# butter.net
KiCad netlist of a schematic drawn in EAGLE
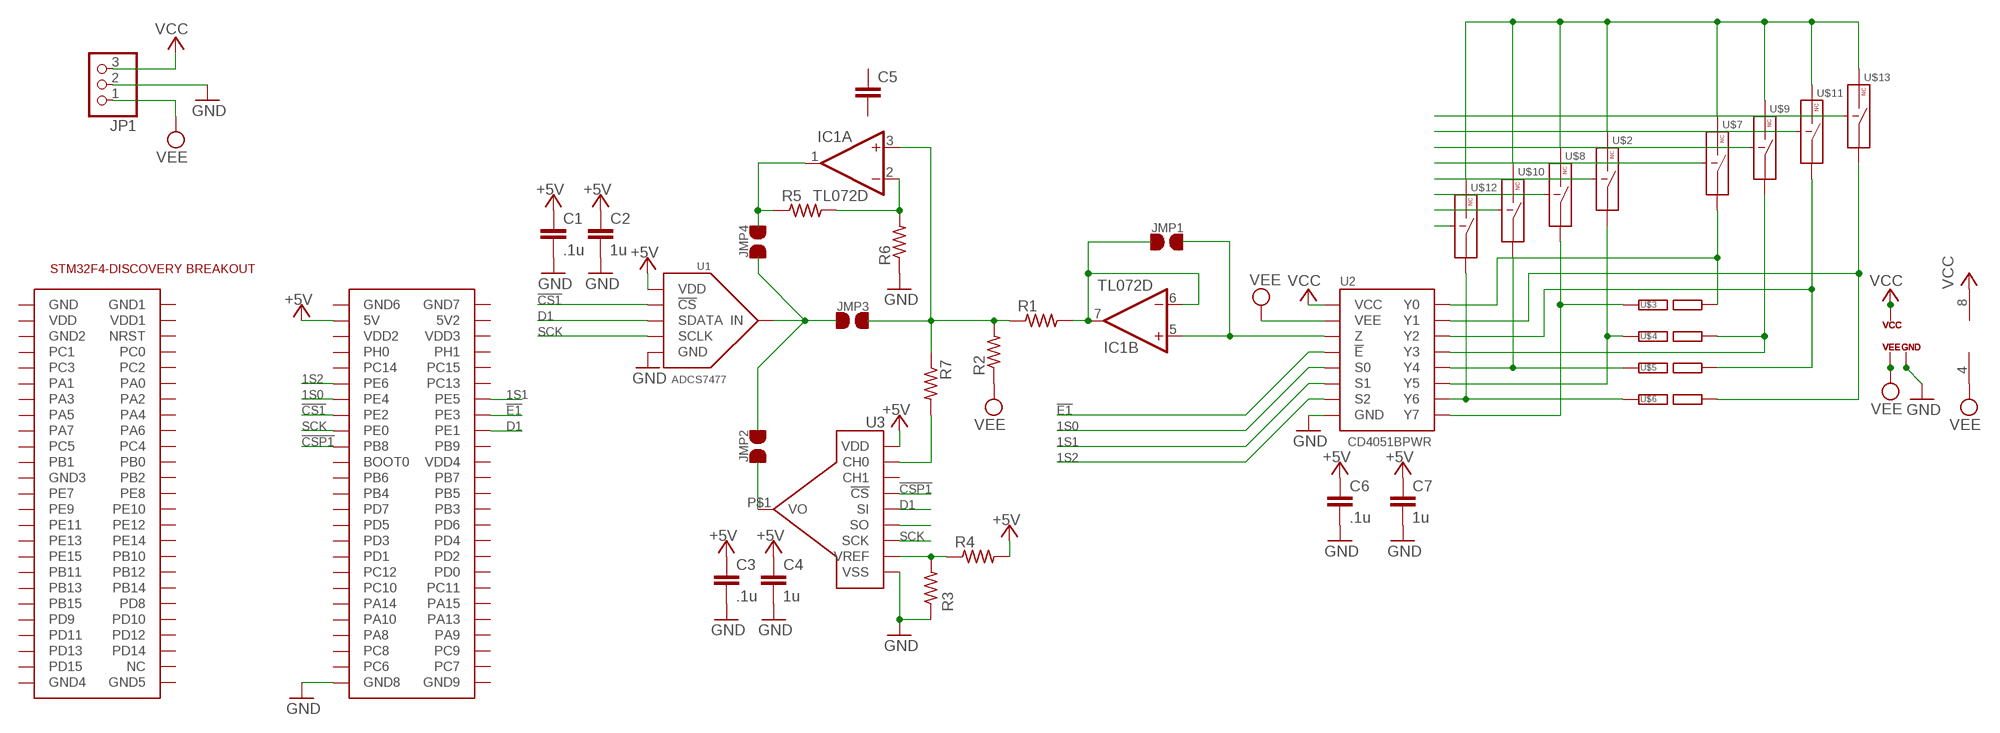
[diagram p0: schematic, sheet 1]

(export (version "E")
  (design (tool "Eeschema 10.0.6"))
  (components
    (comp (ref "C1")
      (value ".1u")
      (footprint "eagle-import:C0805")
      (libsource (lib "eagle-import") (part "C-EUC0805"))
    )
    (comp (ref "C2")
      (value "1u")
      (footprint "eagle-import:C0805")
      (libsource (lib "eagle-import") (part "C-EUC0805"))
    )
    (comp (ref "C3")
      (value ".1u")
      (footprint "eagle-import:C0805")
      (libsource (lib "eagle-import") (part "C-EUC0805"))
    )
    (comp (ref "C4")
      (value "1u")
      (footprint "eagle-import:C0805")
      (libsource (lib "eagle-import") (part "C-EUC0805"))
    )
    (comp (ref "C5")
      (value "C-EUC0805")
      (footprint "eagle-import:C0805")
      (libsource (lib "eagle-import") (part "C-EUC0805"))
    )
    (comp (ref "C6")
      (value ".1u")
      (footprint "eagle-import:C0805")
      (libsource (lib "eagle-import") (part "C-EUC0805"))
    )
    (comp (ref "C7")
      (value "1u")
      (footprint "eagle-import:C0805")
      (libsource (lib "eagle-import") (part "C-EUC0805"))
    )
    (comp (ref "IC1")
      (value "TL072D")
      (footprint "eagle-import:SO08")
      (libsource (lib "eagle-import") (part "TL072D"))
    )
    (comp (ref "JMP1")
      (value "JMP")
      (footprint "eagle-import:JMP")
      (libsource (lib "eagle-import") (part "JMP"))
    )
    (comp (ref "JMP2")
      (value "JMP")
      (footprint "eagle-import:JMP")
      (libsource (lib "eagle-import") (part "JMP"))
    )
    (comp (ref "JMP3")
      (value "JMP")
      (footprint "eagle-import:JMP")
      (libsource (lib "eagle-import") (part "JMP"))
    )
    (comp (ref "JMP4")
      (value "JMP")
      (footprint "eagle-import:JMP")
      (libsource (lib "eagle-import") (part "JMP"))
    )
    (comp (ref "JP1")
      (value "PINHD-1X3")
      (footprint "eagle-import:1X03")
      (libsource (lib "eagle-import") (part "PINHD-1X3"))
    )
    (comp (ref "R1")
      (value "R-US_R0603")
      (footprint "eagle-import:R0603")
      (libsource (lib "eagle-import") (part "R-US_R0603"))
    )
    (comp (ref "R2")
      (value "R-US_R0603")
      (footprint "eagle-import:R0603")
      (libsource (lib "eagle-import") (part "R-US_R0603"))
    )
    (comp (ref "R3")
      (value "R-US_R0603")
      (footprint "eagle-import:R0603")
      (libsource (lib "eagle-import") (part "R-US_R0603"))
    )
    (comp (ref "R4")
      (value "R-US_R0603")
      (footprint "eagle-import:R0603")
      (libsource (lib "eagle-import") (part "R-US_R0603"))
    )
    (comp (ref "R5")
      (value "R-US_R0603")
      (footprint "eagle-import:R0603")
      (libsource (lib "eagle-import") (part "R-US_R0603"))
    )
    (comp (ref "R6")
      (value "R-US_R0603")
      (footprint "eagle-import:R0603")
      (libsource (lib "eagle-import") (part "R-US_R0603"))
    )
    (comp (ref "R7")
      (value "R-US_R0603")
      (footprint "eagle-import:R0603")
      (libsource (lib "eagle-import") (part "R-US_R0603"))
    )
    (comp (ref "U$1")
      (value "STM32F4-DISCOVERY")
      (footprint "eagle-import:STM32F4-DISCOVERY")
      (libsource (lib "eagle-import") (part "STM32F4-DISCOVERY"))
    )
    (comp (ref "U$2")
      (value "DG467")
      (footprint "eagle-import:TSSOP-6")
      (libsource (lib "eagle-import") (part "DG467"))
    )
    (comp (ref "U$3")
      (value "RAILSEP")
      (footprint "eagle-import:RAIL")
      (libsource (lib "eagle-import") (part "RAILSEP"))
    )
    (comp (ref "U$4")
      (value "RAILSEP")
      (footprint "eagle-import:RAIL")
      (libsource (lib "eagle-import") (part "RAILSEP"))
    )
    (comp (ref "U$5")
      (value "RAILSEP")
      (footprint "eagle-import:RAIL")
      (libsource (lib "eagle-import") (part "RAILSEP"))
    )
    (comp (ref "U$6")
      (value "RAILSEP")
      (footprint "eagle-import:RAIL")
      (libsource (lib "eagle-import") (part "RAILSEP"))
    )
    (comp (ref "U$7")
      (value "DG467")
      (footprint "eagle-import:TSSOP-6")
      (libsource (lib "eagle-import") (part "DG467"))
    )
    (comp (ref "U$8")
      (value "DG467")
      (footprint "eagle-import:TSSOP-6")
      (libsource (lib "eagle-import") (part "DG467"))
    )
    (comp (ref "U$9")
      (value "DG467")
      (footprint "eagle-import:TSSOP-6")
      (libsource (lib "eagle-import") (part "DG467"))
    )
    (comp (ref "U$10")
      (value "DG467")
      (footprint "eagle-import:TSSOP-6")
      (libsource (lib "eagle-import") (part "DG467"))
    )
    (comp (ref "U$11")
      (value "DG467")
      (footprint "eagle-import:TSSOP-6")
      (libsource (lib "eagle-import") (part "DG467"))
    )
    (comp (ref "U$12")
      (value "DG467")
      (footprint "eagle-import:TSSOP-6")
      (libsource (lib "eagle-import") (part "DG467"))
    )
    (comp (ref "U$13")
      (value "DG467")
      (footprint "eagle-import:TSSOP-6")
      (libsource (lib "eagle-import") (part "DG467"))
    )
    (comp (ref "U1")
      (value "ADCS7477")
      (footprint "eagle-import:SOT-23-6")
      (libsource (lib "eagle-import") (part "ADCS7477"))
    )
    (comp (ref "U2")
      (value "CD4051BPWR")
      (footprint "eagle-import:TSSOP-16")
      (libsource (lib "eagle-import") (part "CD4051BPWR"))
    )
    (comp (ref "U3")
      (value "MCP6S93")
      (footprint "eagle-import:MSOP-10")
      (libsource (lib "eagle-import") (part "MCP6S93"))
    )
  )
  (nets
    (net (code "1") (name "+5V") (class "Default")
      (node (ref "C1") (pin "1") (pinfunction "1_1") (pintype "passive"))
      (node (ref "C2") (pin "1") (pinfunction "1_1") (pintype "passive"))
      (node (ref "C3") (pin "1") (pinfunction "1_1") (pintype "passive"))
      (node (ref "C4") (pin "1") (pinfunction "1_1") (pintype "passive"))
      (node (ref "C6") (pin "1") (pinfunction "1_1") (pintype "passive"))
      (node (ref "C7") (pin "1") (pinfunction "1_1") (pintype "passive"))
      (node (ref "R4") (pin "2") (pinfunction "2_2") (pintype "passive"))
      (node (ref "U$1") (pin "P$53") (pinfunction "5V_P$53") (pintype "bidirectional"))
      (node (ref "U1") (pin "P$1") (pinfunction "VDD_P$1") (pintype "bidirectional"))
      (node (ref "U3") (pin "P$10") (pinfunction "VDD_P$10") (pintype "bidirectional"))
    )
    (net (code "2") (name "/1S0") (class "Default")
      (node (ref "U$1") (pin "P$63") (pinfunction "PE4_P$63") (pintype "bidirectional"))
      (node (ref "U2") (pin "P$11") (pinfunction "S0_P$11") (pintype "bidirectional"))
    )
    (net (code "3") (name "/1S1") (class "Default")
      (node (ref "U$1") (pin "P$64") (pinfunction "PE5_P$64") (pintype "bidirectional"))
      (node (ref "U2") (pin "P$10") (pinfunction "S1_P$10") (pintype "bidirectional"))
    )
    (net (code "4") (name "/1S2") (class "Default")
      (node (ref "U$1") (pin "P$61") (pinfunction "PE6_P$61") (pintype "bidirectional"))
      (node (ref "U2") (pin "P$9") (pinfunction "S2_P$9") (pintype "bidirectional"))
    )
    (net (code "5") (name "/D1") (class "Default")
      (node (ref "U$1") (pin "P$68") (pinfunction "PE1_P$68") (pintype "bidirectional"))
      (node (ref "U1") (pin "P$5") (pinfunction "SDATA_P$5") (pintype "bidirectional"))
      (node (ref "U3") (pin "P$7") (pinfunction "SI_P$7") (pintype "bidirectional"))
    )
    (net (code "6") (name "/SCK") (class "Default")
      (node (ref "U$1") (pin "P$67") (pinfunction "PE0_P$67") (pintype "bidirectional"))
      (node (ref "U1") (pin "P$4") (pinfunction "SCLK_P$4") (pintype "bidirectional"))
      (node (ref "U3") (pin "P$9") (pinfunction "SCK_P$9") (pintype "bidirectional"))
    )
    (net (code "7") (name "/~{CS1}") (class "Default")
      (node (ref "U$1") (pin "P$65") (pinfunction "PE2_P$65") (pintype "bidirectional"))
      (node (ref "U1") (pin "P$6") (pinfunction "~{CS}_P$6") (pintype "bidirectional"))
    )
    (net (code "8") (name "/~{CSP1}") (class "Default")
      (node (ref "U$1") (pin "P$69") (pinfunction "PB8_P$69") (pintype "bidirectional"))
      (node (ref "U3") (pin "P$6") (pinfunction "~{CS}_P$6") (pintype "bidirectional"))
    )
    (net (code "9") (name "/~{E1}") (class "Default")
      (node (ref "U$1") (pin "P$66") (pinfunction "PE3_P$66") (pintype "bidirectional"))
      (node (ref "U2") (pin "P$6") (pinfunction "~{E}_P$6") (pintype "bidirectional"))
    )
    (net (code "10") (name "GND") (class "Default")
      (node (ref "C1") (pin "2") (pinfunction "2_2") (pintype "passive"))
      (node (ref "C2") (pin "2") (pinfunction "2_2") (pintype "passive"))
      (node (ref "C3") (pin "2") (pinfunction "2_2") (pintype "passive"))
      (node (ref "C4") (pin "2") (pinfunction "2_2") (pintype "passive"))
      (node (ref "C6") (pin "2") (pinfunction "2_2") (pintype "passive"))
      (node (ref "C7") (pin "2") (pinfunction "2_2") (pintype "passive"))
      (node (ref "JP1") (pin "2") (pinfunction "2_2") (pintype "passive"))
      (node (ref "R3") (pin "1") (pinfunction "1_1") (pintype "passive"))
      (node (ref "R6") (pin "1") (pinfunction "1_1") (pintype "passive"))
      (node (ref "U$1") (pin "P$99") (pinfunction "GND8_P$99") (pintype "bidirectional"))
      (node (ref "U$10") (pin "P$4") (pinfunction "GND_P$4") (pintype "bidirectional"))
      (node (ref "U$11") (pin "P$4") (pinfunction "GND_P$4") (pintype "bidirectional"))
      (node (ref "U$12") (pin "P$4") (pinfunction "GND_P$4") (pintype "bidirectional"))
      (node (ref "U$13") (pin "P$4") (pinfunction "GND_P$4") (pintype "bidirectional"))
      (node (ref "U$2") (pin "P$4") (pinfunction "GND_P$4") (pintype "bidirectional"))
      (node (ref "U$7") (pin "P$4") (pinfunction "GND_P$4") (pintype "bidirectional"))
      (node (ref "U$8") (pin "P$4") (pinfunction "GND_P$4") (pintype "bidirectional"))
      (node (ref "U$9") (pin "P$4") (pinfunction "GND_P$4") (pintype "bidirectional"))
      (node (ref "U1") (pin "P$2") (pinfunction "GND_P$2") (pintype "bidirectional"))
      (node (ref "U2") (pin "P$8") (pinfunction "GND_P$8") (pintype "bidirectional"))
      (node (ref "U3") (pin "P$5") (pinfunction "VSS_P$5") (pintype "bidirectional"))
    )
    (net (code "11") (name "Net-(IC1A-+IN)") (class "Default")
      (node (ref "IC1") (pin "3") (pinfunction "+IN_3") (pintype "input"))
      (node (ref "JMP3") (pin "P$2") (pinfunction "P$2_P$2") (pintype "bidirectional"))
      (node (ref "R1") (pin "1") (pinfunction "1_1") (pintype "passive"))
      (node (ref "R2") (pin "2") (pinfunction "2_2") (pintype "passive"))
      (node (ref "R7") (pin "1") (pinfunction "1_1") (pintype "passive"))
    )
    (net (code "12") (name "Net-(IC1A--IN)") (class "Default")
      (node (ref "IC1") (pin "2") (pinfunction "-IN_2") (pintype "input"))
      (node (ref "R5") (pin "2") (pinfunction "2_2") (pintype "passive"))
      (node (ref "R6") (pin "2") (pinfunction "2_2") (pintype "passive"))
    )
    (net (code "13") (name "Net-(IC1A-OUT)") (class "Default")
      (node (ref "IC1") (pin "1") (pinfunction "OUT_1") (pintype "output"))
      (node (ref "JMP4") (pin "P$2") (pinfunction "P$2_P$2") (pintype "bidirectional"))
      (node (ref "R5") (pin "1") (pinfunction "1_1") (pintype "passive"))
    )
    (net (code "14") (name "Net-(IC1B-+IN)") (class "Default")
      (node (ref "IC1") (pin "5") (pinfunction "+IN_5") (pintype "input"))
      (node (ref "JMP1") (pin "P$2") (pinfunction "P$2_P$2") (pintype "bidirectional"))
      (node (ref "U2") (pin "P$3") (pinfunction "Z_P$3") (pintype "bidirectional"))
    )
    (net (code "15") (name "Net-(IC1B--IN)") (class "Default")
      (node (ref "IC1") (pin "6") (pinfunction "-IN_6") (pintype "input"))
      (node (ref "IC1") (pin "7") (pinfunction "OUT_7") (pintype "output"))
      (node (ref "JMP1") (pin "P$1") (pinfunction "P$1_P$1") (pintype "bidirectional"))
      (node (ref "R1") (pin "2") (pinfunction "2_2") (pintype "passive"))
    )
    (net (code "16") (name "Net-(U$2A-COM)") (class "Default")
      (node (ref "U$2") (pin "P$6") (pinfunction "COM_P$6") (pintype "bidirectional"))
      (node (ref "U$4") (pin "P$L") (pinfunction "L_P$L") (pintype "bidirectional"))
      (node (ref "U2") (pin "P$5") (pinfunction "Y5_P$5") (pintype "bidirectional"))
    )
    (net (code "17") (name "Net-(U$3-L)") (class "Default")
      (node (ref "U$3") (pin "P$L") (pinfunction "L_P$L") (pintype "bidirectional"))
      (node (ref "U$8") (pin "P$6") (pinfunction "COM_P$6") (pintype "bidirectional"))
      (node (ref "U2") (pin "P$4") (pinfunction "Y7_P$4") (pintype "bidirectional"))
    )
    (net (code "18") (name "Net-(U$3-R)") (class "Default")
      (node (ref "U$3") (pin "P$R") (pinfunction "R_P$R") (pintype "bidirectional"))
      (node (ref "U$7") (pin "P$6") (pinfunction "COM_P$6") (pintype "bidirectional"))
      (node (ref "U2") (pin "P$13") (pinfunction "Y0_P$13") (pintype "bidirectional"))
    )
    (net (code "19") (name "Net-(U$4-R)") (class "Default")
      (node (ref "U$4") (pin "P$R") (pinfunction "R_P$R") (pintype "bidirectional"))
      (node (ref "U$9") (pin "P$6") (pinfunction "COM_P$6") (pintype "bidirectional"))
      (node (ref "U2") (pin "P$12") (pinfunction "Y3_P$12") (pintype "bidirectional"))
    )
    (net (code "20") (name "Net-(U$10A-COM)") (class "Default")
      (node (ref "U$10") (pin "P$6") (pinfunction "COM_P$6") (pintype "bidirectional"))
      (node (ref "U$5") (pin "P$L") (pinfunction "L_P$L") (pintype "bidirectional"))
      (node (ref "U2") (pin "P$1") (pinfunction "Y4_P$1") (pintype "bidirectional"))
    )
    (net (code "21") (name "Net-(U$10A-IN)") (class "Default")
      (node (ref "U$10") (pin "P$1") (pinfunction "IN_P$1") (pintype "bidirectional"))
      (node (ref "U$11") (pin "P$1") (pinfunction "IN_P$1") (pintype "bidirectional"))
      (node (ref "U$12") (pin "P$1") (pinfunction "IN_P$1") (pintype "bidirectional"))
      (node (ref "U$13") (pin "P$1") (pinfunction "IN_P$1") (pintype "bidirectional"))
      (node (ref "U$2") (pin "P$1") (pinfunction "IN_P$1") (pintype "bidirectional"))
      (node (ref "U$7") (pin "P$1") (pinfunction "IN_P$1") (pintype "bidirectional"))
      (node (ref "U$8") (pin "P$1") (pinfunction "IN_P$1") (pintype "bidirectional"))
      (node (ref "U$9") (pin "P$1") (pinfunction "IN_P$1") (pintype "bidirectional"))
    )
    (net (code "22") (name "Net-(U$11A-COM)") (class "Default")
      (node (ref "U$11") (pin "P$6") (pinfunction "COM_P$6") (pintype "bidirectional"))
      (node (ref "U$5") (pin "P$R") (pinfunction "R_P$R") (pintype "bidirectional"))
      (node (ref "U2") (pin "P$15") (pinfunction "Y2_P$15") (pintype "bidirectional"))
    )
    (net (code "23") (name "Net-(U$12A-COM)") (class "Default")
      (node (ref "U$12") (pin "P$6") (pinfunction "COM_P$6") (pintype "bidirectional"))
      (node (ref "U$6") (pin "P$L") (pinfunction "L_P$L") (pintype "bidirectional"))
      (node (ref "U2") (pin "P$2") (pinfunction "Y6_P$2") (pintype "bidirectional"))
    )
    (net (code "24") (name "Net-(U$13A-COM)") (class "Default")
      (node (ref "U$13") (pin "P$6") (pinfunction "COM_P$6") (pintype "bidirectional"))
      (node (ref "U$6") (pin "P$R") (pinfunction "R_P$R") (pintype "bidirectional"))
      (node (ref "U2") (pin "P$14") (pinfunction "Y1_P$14") (pintype "bidirectional"))
    )
    (net (code "25") (name "Net-(U1-IN)") (class "Default")
      (node (ref "JMP2") (pin "P$2") (pinfunction "P$2_P$2") (pintype "bidirectional"))
      (node (ref "JMP3") (pin "P$1") (pinfunction "P$1_P$1") (pintype "bidirectional"))
      (node (ref "JMP4") (pin "P$1") (pinfunction "P$1_P$1") (pintype "bidirectional"))
      (node (ref "U1") (pin "P$3") (pinfunction "IN_P$3") (pintype "bidirectional"))
    )
    (net (code "26") (name "Net-(U3-CH0)") (class "Default")
      (node (ref "R7") (pin "2") (pinfunction "2_2") (pintype "passive"))
      (node (ref "U3") (pin "P$2") (pinfunction "CH0_P$2") (pintype "bidirectional"))
    )
    (net (code "27") (name "Net-(U3-VO)") (class "Default")
      (node (ref "JMP2") (pin "P$1") (pinfunction "P$1_P$1") (pintype "bidirectional"))
      (node (ref "U3") (pin "P$1") (pinfunction "VO_P$1") (pintype "bidirectional"))
    )
    (net (code "28") (name "Net-(U3-VREF)") (class "Default")
      (node (ref "R3") (pin "2") (pinfunction "2_2") (pintype "passive"))
      (node (ref "R4") (pin "1") (pinfunction "1_1") (pintype "passive"))
      (node (ref "U3") (pin "P$4") (pinfunction "VREF_P$4") (pintype "bidirectional"))
    )
    (net (code "29") (name "VCC") (class "Default")
      (node (ref "IC1") (pin "8") (pinfunction "V+_8") (pintype "power_in"))
      (node (ref "JP1") (pin "3") (pinfunction "3_3") (pintype "passive"))
      (node (ref "U$10") (pin "P$5") (pinfunction "VCC_P$5") (pintype "bidirectional"))
      (node (ref "U$11") (pin "P$5") (pinfunction "VCC_P$5") (pintype "bidirectional"))
      (node (ref "U$12") (pin "P$5") (pinfunction "VCC_P$5") (pintype "bidirectional"))
      (node (ref "U$13") (pin "P$5") (pinfunction "VCC_P$5") (pintype "bidirectional"))
      (node (ref "U$2") (pin "P$5") (pinfunction "VCC_P$5") (pintype "bidirectional"))
      (node (ref "U$7") (pin "P$5") (pinfunction "VCC_P$5") (pintype "bidirectional"))
      (node (ref "U$8") (pin "P$5") (pinfunction "VCC_P$5") (pintype "bidirectional"))
      (node (ref "U$9") (pin "P$5") (pinfunction "VCC_P$5") (pintype "bidirectional"))
      (node (ref "U2") (pin "P$16") (pinfunction "VCC_P$16") (pintype "bidirectional"))
    )
    (net (code "30") (name "VEE") (class "Default")
      (node (ref "IC1") (pin "4") (pinfunction "V-_4") (pintype "power_in"))
      (node (ref "JP1") (pin "1") (pinfunction "1_1") (pintype "passive"))
      (node (ref "R2") (pin "1") (pinfunction "1_1") (pintype "passive"))
      (node (ref "U$10") (pin "P$2") (pinfunction "VEE_P$2") (pintype "bidirectional"))
      (node (ref "U$11") (pin "P$2") (pinfunction "VEE_P$2") (pintype "bidirectional"))
      (node (ref "U$12") (pin "P$2") (pinfunction "VEE_P$2") (pintype "bidirectional"))
      (node (ref "U$13") (pin "P$2") (pinfunction "VEE_P$2") (pintype "bidirectional"))
      (node (ref "U$2") (pin "P$2") (pinfunction "VEE_P$2") (pintype "bidirectional"))
      (node (ref "U$7") (pin "P$2") (pinfunction "VEE_P$2") (pintype "bidirectional"))
      (node (ref "U$8") (pin "P$2") (pinfunction "VEE_P$2") (pintype "bidirectional"))
      (node (ref "U$9") (pin "P$2") (pinfunction "VEE_P$2") (pintype "bidirectional"))
      (node (ref "U2") (pin "P$7") (pinfunction "VEE_P$7") (pintype "bidirectional"))
    )
    (net (code "31") (name "unconnected-(C5-Pad1)") (class "Default")
      (node (ref "C5") (pin "1") (pinfunction "1_1") (pintype "passive"))
    )
    (net (code "32") (name "unconnected-(C5-Pad2)") (class "Default")
      (node (ref "C5") (pin "2") (pinfunction "2_2") (pintype "passive"))
    )
    (net (code "33") (name "unconnected-(U$1-5V2-PadP$54)") (class "Default")
      (node (ref "U$1") (pin "P$54") (pinfunction "5V2_P$54") (pintype "bidirectional"))
    )
    (net (code "34") (name "unconnected-(U$1-BOOT0-PadP$71)") (class "Default")
      (node (ref "U$1") (pin "P$71") (pinfunction "BOOT0_P$71") (pintype "bidirectional"))
    )
    (net (code "35") (name "unconnected-(U$1-GND-PadP$1)") (class "Default")
      (node (ref "U$1") (pin "P$1") (pinfunction "GND_P$1") (pintype "bidirectional"))
    )
    (net (code "36") (name "unconnected-(U$1-GND1-PadP$2)") (class "Default")
      (node (ref "U$1") (pin "P$2") (pinfunction "GND1_P$2") (pintype "bidirectional"))
    )
    (net (code "37") (name "unconnected-(U$1-GND2-PadP$5)") (class "Default")
      (node (ref "U$1") (pin "P$5") (pinfunction "GND2_P$5") (pintype "bidirectional"))
    )
    (net (code "38") (name "unconnected-(U$1-GND3-PadP$23)") (class "Default")
      (node (ref "U$1") (pin "P$23") (pinfunction "GND3_P$23") (pintype "bidirectional"))
    )
    (net (code "39") (name "unconnected-(U$1-GND4-PadP$49)") (class "Default")
      (node (ref "U$1") (pin "P$49") (pinfunction "GND4_P$49") (pintype "bidirectional"))
    )
    (net (code "40") (name "unconnected-(U$1-GND5-PadP$50)") (class "Default")
      (node (ref "U$1") (pin "P$50") (pinfunction "GND5_P$50") (pintype "bidirectional"))
    )
    (net (code "41") (name "unconnected-(U$1-GND6-PadP$51)") (class "Default")
      (node (ref "U$1") (pin "P$51") (pinfunction "GND6_P$51") (pintype "bidirectional"))
    )
    (net (code "42") (name "unconnected-(U$1-GND7-PadP$52)") (class "Default")
      (node (ref "U$1") (pin "P$52") (pinfunction "GND7_P$52") (pintype "bidirectional"))
    )
    (net (code "43") (name "unconnected-(U$1-GND9-PadP$100)") (class "Default")
      (node (ref "U$1") (pin "P$100") (pinfunction "GND9_P$100") (pintype "bidirectional"))
    )
    (net (code "44") (name "unconnected-(U$1-NC-PadP$48)") (class "Default")
      (node (ref "U$1") (pin "P$48") (pinfunction "NC_P$48") (pintype "bidirectional"))
    )
    (net (code "45") (name "unconnected-(U$1-NRST-PadP$6)") (class "Default")
      (node (ref "U$1") (pin "P$6") (pinfunction "NRST_P$6") (pintype "bidirectional"))
    )
    (net (code "46") (name "unconnected-(U$1-PA0-PadP$12)") (class "Default")
      (node (ref "U$1") (pin "P$12") (pinfunction "PA0_P$12") (pintype "bidirectional"))
    )
    (net (code "47") (name "unconnected-(U$1-PA1-PadP$11)") (class "Default")
      (node (ref "U$1") (pin "P$11") (pinfunction "PA1_P$11") (pintype "bidirectional"))
    )
    (net (code "48") (name "unconnected-(U$1-PA2-PadP$14)") (class "Default")
      (node (ref "U$1") (pin "P$14") (pinfunction "PA2_P$14") (pintype "bidirectional"))
    )
    (net (code "49") (name "unconnected-(U$1-PA3-PadP$13)") (class "Default")
      (node (ref "U$1") (pin "P$13") (pinfunction "PA3_P$13") (pintype "bidirectional"))
    )
    (net (code "50") (name "unconnected-(U$1-PA4-PadP$16)") (class "Default")
      (node (ref "U$1") (pin "P$16") (pinfunction "PA4_P$16") (pintype "bidirectional"))
    )
    (net (code "51") (name "unconnected-(U$1-PA5-PadP$15)") (class "Default")
      (node (ref "U$1") (pin "P$15") (pinfunction "PA5_P$15") (pintype "bidirectional"))
    )
    (net (code "52") (name "unconnected-(U$1-PA6-PadP$18)") (class "Default")
      (node (ref "U$1") (pin "P$18") (pinfunction "PA6_P$18") (pintype "bidirectional"))
    )
    (net (code "53") (name "unconnected-(U$1-PA7-PadP$17)") (class "Default")
      (node (ref "U$1") (pin "P$17") (pinfunction "PA7_P$17") (pintype "bidirectional"))
    )
    (net (code "54") (name "unconnected-(U$1-PA8-PadP$93)") (class "Default")
      (node (ref "U$1") (pin "P$93") (pinfunction "PA8_P$93") (pintype "bidirectional"))
    )
    (net (code "55") (name "unconnected-(U$1-PA9-PadP$94)") (class "Default")
      (node (ref "U$1") (pin "P$94") (pinfunction "PA9_P$94") (pintype "bidirectional"))
    )
    (net (code "56") (name "unconnected-(U$1-PA10-PadP$91)") (class "Default")
      (node (ref "U$1") (pin "P$91") (pinfunction "PA10_P$91") (pintype "bidirectional"))
    )
    (net (code "57") (name "unconnected-(U$1-PA13-PadP$92)") (class "Default")
      (node (ref "U$1") (pin "P$92") (pinfunction "PA13_P$92") (pintype "bidirectional"))
    )
    (net (code "58") (name "unconnected-(U$1-PA14-PadP$89)") (class "Default")
      (node (ref "U$1") (pin "P$89") (pinfunction "PA14_P$89") (pintype "bidirectional"))
    )
    (net (code "59") (name "unconnected-(U$1-PA15-PadP$90)") (class "Default")
      (node (ref "U$1") (pin "P$90") (pinfunction "PA15_P$90") (pintype "bidirectional"))
    )
    (net (code "60") (name "unconnected-(U$1-PB0-PadP$22)") (class "Default")
      (node (ref "U$1") (pin "P$22") (pinfunction "PB0_P$22") (pintype "bidirectional"))
    )
    (net (code "61") (name "unconnected-(U$1-PB1-PadP$21)") (class "Default")
      (node (ref "U$1") (pin "P$21") (pinfunction "PB1_P$21") (pintype "bidirectional"))
    )
    (net (code "62") (name "unconnected-(U$1-PB2-PadP$24)") (class "Default")
      (node (ref "U$1") (pin "P$24") (pinfunction "PB2_P$24") (pintype "bidirectional"))
    )
    (net (code "63") (name "unconnected-(U$1-PB3-PadP$78)") (class "Default")
      (node (ref "U$1") (pin "P$78") (pinfunction "PB3_P$78") (pintype "bidirectional"))
    )
    (net (code "64") (name "unconnected-(U$1-PB4-PadP$75)") (class "Default")
      (node (ref "U$1") (pin "P$75") (pinfunction "PB4_P$75") (pintype "bidirectional"))
    )
    (net (code "65") (name "unconnected-(U$1-PB5-PadP$76)") (class "Default")
      (node (ref "U$1") (pin "P$76") (pinfunction "PB5_P$76") (pintype "bidirectional"))
    )
    (net (code "66") (name "unconnected-(U$1-PB6-PadP$73)") (class "Default")
      (node (ref "U$1") (pin "P$73") (pinfunction "PB6_P$73") (pintype "bidirectional"))
    )
    (net (code "67") (name "unconnected-(U$1-PB7-PadP$74)") (class "Default")
      (node (ref "U$1") (pin "P$74") (pinfunction "PB7_P$74") (pintype "bidirectional"))
    )
    (net (code "68") (name "unconnected-(U$1-PB9-PadP$70)") (class "Default")
      (node (ref "U$1") (pin "P$70") (pinfunction "PB9_P$70") (pintype "bidirectional"))
    )
    (net (code "69") (name "unconnected-(U$1-PB10-PadP$34)") (class "Default")
      (node (ref "U$1") (pin "P$34") (pinfunction "PB10_P$34") (pintype "bidirectional"))
    )
    (net (code "70") (name "unconnected-(U$1-PB11-PadP$35)") (class "Default")
      (node (ref "U$1") (pin "P$35") (pinfunction "PB11_P$35") (pintype "bidirectional"))
    )
    (net (code "71") (name "unconnected-(U$1-PB12-PadP$36)") (class "Default")
      (node (ref "U$1") (pin "P$36") (pinfunction "PB12_P$36") (pintype "bidirectional"))
    )
    (net (code "72") (name "unconnected-(U$1-PB13-PadP$37)") (class "Default")
      (node (ref "U$1") (pin "P$37") (pinfunction "PB13_P$37") (pintype "bidirectional"))
    )
    (net (code "73") (name "unconnected-(U$1-PB14-PadP$38)") (class "Default")
      (node (ref "U$1") (pin "P$38") (pinfunction "PB14_P$38") (pintype "bidirectional"))
    )
    (net (code "74") (name "unconnected-(U$1-PB15-PadP$39)") (class "Default")
      (node (ref "U$1") (pin "P$39") (pinfunction "PB15_P$39") (pintype "bidirectional"))
    )
    (net (code "75") (name "unconnected-(U$1-PC0-PadP$8)") (class "Default")
      (node (ref "U$1") (pin "P$8") (pinfunction "PC0_P$8") (pintype "bidirectional"))
    )
    (net (code "76") (name "unconnected-(U$1-PC1-PadP$7)") (class "Default")
      (node (ref "U$1") (pin "P$7") (pinfunction "PC1_P$7") (pintype "bidirectional"))
    )
    (net (code "77") (name "unconnected-(U$1-PC2-PadP$10)") (class "Default")
      (node (ref "U$1") (pin "P$10") (pinfunction "PC2_P$10") (pintype "bidirectional"))
    )
    (net (code "78") (name "unconnected-(U$1-PC3-PadP$9)") (class "Default")
      (node (ref "U$1") (pin "P$9") (pinfunction "PC3_P$9") (pintype "bidirectional"))
    )
    (net (code "79") (name "unconnected-(U$1-PC4-PadP$20)") (class "Default")
      (node (ref "U$1") (pin "P$20") (pinfunction "PC4_P$20") (pintype "bidirectional"))
    )
    (net (code "80") (name "unconnected-(U$1-PC5-PadP$19)") (class "Default")
      (node (ref "U$1") (pin "P$19") (pinfunction "PC5_P$19") (pintype "bidirectional"))
    )
    (net (code "81") (name "unconnected-(U$1-PC6-PadP$97)") (class "Default")
      (node (ref "U$1") (pin "P$97") (pinfunction "PC6_P$97") (pintype "bidirectional"))
    )
    (net (code "82") (name "unconnected-(U$1-PC7-PadP$98)") (class "Default")
      (node (ref "U$1") (pin "P$98") (pinfunction "PC7_P$98") (pintype "bidirectional"))
    )
    (net (code "83") (name "unconnected-(U$1-PC8-PadP$95)") (class "Default")
      (node (ref "U$1") (pin "P$95") (pinfunction "PC8_P$95") (pintype "bidirectional"))
    )
    (net (code "84") (name "unconnected-(U$1-PC9-PadP$96)") (class "Default")
      (node (ref "U$1") (pin "P$96") (pinfunction "PC9_P$96") (pintype "bidirectional"))
    )
    (net (code "85") (name "unconnected-(U$1-PC10-PadP$87)") (class "Default")
      (node (ref "U$1") (pin "P$87") (pinfunction "PC10_P$87") (pintype "bidirectional"))
    )
    (net (code "86") (name "unconnected-(U$1-PC11-PadP$88)") (class "Default")
      (node (ref "U$1") (pin "P$88") (pinfunction "PC11_P$88") (pintype "bidirectional"))
    )
    (net (code "87") (name "unconnected-(U$1-PC12-PadP$85)") (class "Default")
      (node (ref "U$1") (pin "P$85") (pinfunction "PC12_P$85") (pintype "bidirectional"))
    )
    (net (code "88") (name "unconnected-(U$1-PC13-PadP$62)") (class "Default")
      (node (ref "U$1") (pin "P$62") (pinfunction "PC13_P$62") (pintype "bidirectional"))
    )
    (net (code "89") (name "unconnected-(U$1-PC14-PadP$59)") (class "Default")
      (node (ref "U$1") (pin "P$59") (pinfunction "PC14_P$59") (pintype "bidirectional"))
    )
    (net (code "90") (name "unconnected-(U$1-PC15-PadP$60)") (class "Default")
      (node (ref "U$1") (pin "P$60") (pinfunction "PC15_P$60") (pintype "bidirectional"))
    )
    (net (code "91") (name "unconnected-(U$1-PD0-PadP$86)") (class "Default")
      (node (ref "U$1") (pin "P$86") (pinfunction "PD0_P$86") (pintype "bidirectional"))
    )
    (net (code "92") (name "unconnected-(U$1-PD1-PadP$83)") (class "Default")
      (node (ref "U$1") (pin "P$83") (pinfunction "PD1_P$83") (pintype "bidirectional"))
    )
    (net (code "93") (name "unconnected-(U$1-PD2-PadP$84)") (class "Default")
      (node (ref "U$1") (pin "P$84") (pinfunction "PD2_P$84") (pintype "bidirectional"))
    )
    (net (code "94") (name "unconnected-(U$1-PD3-PadP$81)") (class "Default")
      (node (ref "U$1") (pin "P$81") (pinfunction "PD3_P$81") (pintype "bidirectional"))
    )
    (net (code "95") (name "unconnected-(U$1-PD4-PadP$82)") (class "Default")
      (node (ref "U$1") (pin "P$82") (pinfunction "PD4_P$82") (pintype "bidirectional"))
    )
    (net (code "96") (name "unconnected-(U$1-PD5-PadP$79)") (class "Default")
      (node (ref "U$1") (pin "P$79") (pinfunction "PD5_P$79") (pintype "bidirectional"))
    )
    (net (code "97") (name "unconnected-(U$1-PD6-PadP$80)") (class "Default")
      (node (ref "U$1") (pin "P$80") (pinfunction "PD6_P$80") (pintype "bidirectional"))
    )
    (net (code "98") (name "unconnected-(U$1-PD7-PadP$77)") (class "Default")
      (node (ref "U$1") (pin "P$77") (pinfunction "PD7_P$77") (pintype "bidirectional"))
    )
    (net (code "99") (name "unconnected-(U$1-PD8-PadP$40)") (class "Default")
      (node (ref "U$1") (pin "P$40") (pinfunction "PD8_P$40") (pintype "bidirectional"))
    )
    (net (code "100") (name "unconnected-(U$1-PD9-PadP$41)") (class "Default")
      (node (ref "U$1") (pin "P$41") (pinfunction "PD9_P$41") (pintype "bidirectional"))
    )
    (net (code "101") (name "unconnected-(U$1-PD10-PadP$42)") (class "Default")
      (node (ref "U$1") (pin "P$42") (pinfunction "PD10_P$42") (pintype "bidirectional"))
    )
    (net (code "102") (name "unconnected-(U$1-PD11-PadP$43)") (class "Default")
      (node (ref "U$1") (pin "P$43") (pinfunction "PD11_P$43") (pintype "bidirectional"))
    )
    (net (code "103") (name "unconnected-(U$1-PD12-PadP$44)") (class "Default")
      (node (ref "U$1") (pin "P$44") (pinfunction "PD12_P$44") (pintype "bidirectional"))
    )
    (net (code "104") (name "unconnected-(U$1-PD13-PadP$45)") (class "Default")
      (node (ref "U$1") (pin "P$45") (pinfunction "PD13_P$45") (pintype "bidirectional"))
    )
    (net (code "105") (name "unconnected-(U$1-PD14-PadP$46)") (class "Default")
      (node (ref "U$1") (pin "P$46") (pinfunction "PD14_P$46") (pintype "bidirectional"))
    )
    (net (code "106") (name "unconnected-(U$1-PD15-PadP$47)") (class "Default")
      (node (ref "U$1") (pin "P$47") (pinfunction "PD15_P$47") (pintype "bidirectional"))
    )
    (net (code "107") (name "unconnected-(U$1-PE7-PadP$25)") (class "Default")
      (node (ref "U$1") (pin "P$25") (pinfunction "PE7_P$25") (pintype "bidirectional"))
    )
    (net (code "108") (name "unconnected-(U$1-PE8-PadP$26)") (class "Default")
      (node (ref "U$1") (pin "P$26") (pinfunction "PE8_P$26") (pintype "bidirectional"))
    )
    (net (code "109") (name "unconnected-(U$1-PE9-PadP$27)") (class "Default")
      (node (ref "U$1") (pin "P$27") (pinfunction "PE9_P$27") (pintype "bidirectional"))
    )
    (net (code "110") (name "unconnected-(U$1-PE10-PadP$28)") (class "Default")
      (node (ref "U$1") (pin "P$28") (pinfunction "PE10_P$28") (pintype "bidirectional"))
    )
    (net (code "111") (name "unconnected-(U$1-PE11-PadP$29)") (class "Default")
      (node (ref "U$1") (pin "P$29") (pinfunction "PE11_P$29") (pintype "bidirectional"))
    )
    (net (code "112") (name "unconnected-(U$1-PE12-PadP$30)") (class "Default")
      (node (ref "U$1") (pin "P$30") (pinfunction "PE12_P$30") (pintype "bidirectional"))
    )
    (net (code "113") (name "unconnected-(U$1-PE13-PadP$31)") (class "Default")
      (node (ref "U$1") (pin "P$31") (pinfunction "PE13_P$31") (pintype "bidirectional"))
    )
    (net (code "114") (name "unconnected-(U$1-PE14-PadP$32)") (class "Default")
      (node (ref "U$1") (pin "P$32") (pinfunction "PE14_P$32") (pintype "bidirectional"))
    )
    (net (code "115") (name "unconnected-(U$1-PE15-PadP$33)") (class "Default")
      (node (ref "U$1") (pin "P$33") (pinfunction "PE15_P$33") (pintype "bidirectional"))
    )
    (net (code "116") (name "unconnected-(U$1-PH0-PadP$57)") (class "Default")
      (node (ref "U$1") (pin "P$57") (pinfunction "PH0_P$57") (pintype "bidirectional"))
    )
    (net (code "117") (name "unconnected-(U$1-PH1-PadP$58)") (class "Default")
      (node (ref "U$1") (pin "P$58") (pinfunction "PH1_P$58") (pintype "bidirectional"))
    )
    (net (code "118") (name "unconnected-(U$1-VDD-PadP$3)") (class "Default")
      (node (ref "U$1") (pin "P$3") (pinfunction "VDD_P$3") (pintype "bidirectional"))
    )
    (net (code "119") (name "unconnected-(U$1-VDD1-PadP$4)") (class "Default")
      (node (ref "U$1") (pin "P$4") (pinfunction "VDD1_P$4") (pintype "bidirectional"))
    )
    (net (code "120") (name "unconnected-(U$1-VDD2-PadP$55)") (class "Default")
      (node (ref "U$1") (pin "P$55") (pinfunction "VDD2_P$55") (pintype "bidirectional"))
    )
    (net (code "121") (name "unconnected-(U$1-VDD3-PadP$56)") (class "Default")
      (node (ref "U$1") (pin "P$56") (pinfunction "VDD3_P$56") (pintype "bidirectional"))
    )
    (net (code "122") (name "unconnected-(U$1-VDD4-PadP$72)") (class "Default")
      (node (ref "U$1") (pin "P$72") (pinfunction "VDD4_P$72") (pintype "bidirectional"))
    )
    (net (code "123") (name "unconnected-(U$2A-CTL-PadP$3)") (class "Default")
      (node (ref "U$2") (pin "P$3") (pinfunction "CTL_P$3") (pintype "bidirectional"))
    )
    (net (code "124") (name "unconnected-(U$7A-CTL-PadP$3)") (class "Default")
      (node (ref "U$7") (pin "P$3") (pinfunction "CTL_P$3") (pintype "bidirectional"))
    )
    (net (code "125") (name "unconnected-(U$8A-CTL-PadP$3)") (class "Default")
      (node (ref "U$8") (pin "P$3") (pinfunction "CTL_P$3") (pintype "bidirectional"))
    )
    (net (code "126") (name "unconnected-(U$9A-CTL-PadP$3)") (class "Default")
      (node (ref "U$9") (pin "P$3") (pinfunction "CTL_P$3") (pintype "bidirectional"))
    )
    (net (code "127") (name "unconnected-(U$10A-CTL-PadP$3)") (class "Default")
      (node (ref "U$10") (pin "P$3") (pinfunction "CTL_P$3") (pintype "bidirectional"))
    )
    (net (code "128") (name "unconnected-(U$11A-CTL-PadP$3)") (class "Default")
      (node (ref "U$11") (pin "P$3") (pinfunction "CTL_P$3") (pintype "bidirectional"))
    )
    (net (code "129") (name "unconnected-(U$12A-CTL-PadP$3)") (class "Default")
      (node (ref "U$12") (pin "P$3") (pinfunction "CTL_P$3") (pintype "bidirectional"))
    )
    (net (code "130") (name "unconnected-(U$13A-CTL-PadP$3)") (class "Default")
      (node (ref "U$13") (pin "P$3") (pinfunction "CTL_P$3") (pintype "bidirectional"))
    )
    (net (code "131") (name "unconnected-(U3-CH1-PadP$3)") (class "Default")
      (node (ref "U3") (pin "P$3") (pinfunction "CH1_P$3") (pintype "bidirectional"))
    )
    (net (code "132") (name "unconnected-(U3-SO-PadP$8)") (class "Default")
      (node (ref "U3") (pin "P$8") (pinfunction "SO_P$8") (pintype "bidirectional"))
    )
  )
)
